# 2364_Adapter.net
KiCad netlist of a schematic drawn in Altium Designer
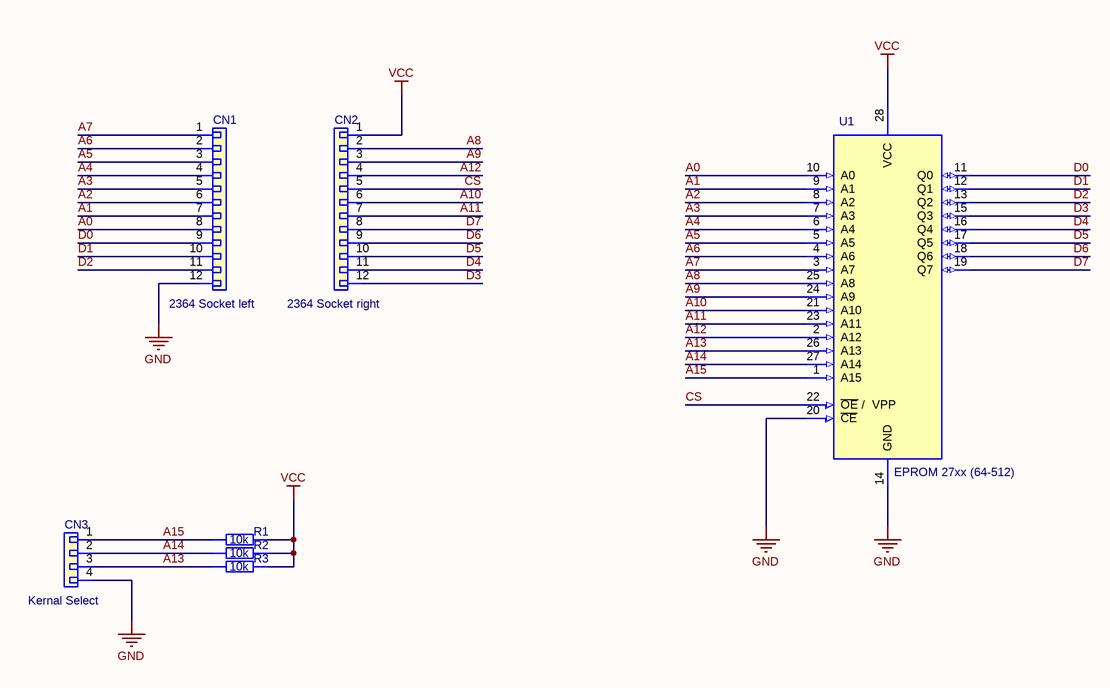
[diagram p0: 2364 Adapter.SchDoc]

(export (version "E")
  (design (tool "Eeschema 10.0.6"))
  (components
    (comp (ref "CN1")
      (value "2364 Socket left")
      (footprint "Pin Header 01x12 2.54mm Horizontal Male")
      (description "CONN HEADER .100 SNGL STR 12POS")
      (libsource (lib "") (part "CONN 01x12_1"))
    )
    (comp (ref "CN2")
      (value "2364 Socket right")
      (footprint "Pin Header 01x12 2.54mm Horizontal Male")
      (description "CONN HEADER .100 SNGL STR 12POS")
      (libsource (lib "PCB-Tech Cloud") (part "CONN 01x12"))
    )
    (comp (ref "CN3")
      (value "Kernal Select")
      (footprint "Pin Header 01x04 2.54mm Horizontal Male")
      (description "CONN HEADER .100\" SNGL STR 4POS")
      (libsource (lib "PCB-Tech Cloud") (part "CONN 01x04"))
    )
    (comp (ref "R1")
      (value "10k")
      (footprint "10 kOhm R Axial DIN0207 L6.3mm D2.5mm P7.62mm Horizontal")
      (description "RES 10K OHM 1/4W 5% AXIAL")
      (fields (field (name "TOLERANCE") "5%"))
      (libsource (lib "PCB-Tech Cloud") (part "Resistor"))
    )
    (comp (ref "R2")
      (value "10k")
      (footprint "10 kOhm R Axial DIN0207 L6.3mm D2.5mm P7.62mm Horizontal")
      (description "RES 10K OHM 1/4W 5% AXIAL")
      (fields (field (name "TOLERANCE") "5%"))
      (libsource (lib "PCB-Tech Cloud") (part "Resistor"))
    )
    (comp (ref "R3")
      (value "10k")
      (footprint "10 kOhm R Axial DIN0207 L6.3mm D2.5mm P7.62mm Horizontal")
      (description "RES 10K OHM 1/4W 5% AXIAL")
      (fields (field (name "TOLERANCE") "5%"))
      (libsource (lib "PCB-Tech Cloud") (part "Resistor"))
    )
    (comp (ref "U1")
      (value "EPROM 27xx (64-512)")
      (footprint "Winbond W27C512-45Z DIP-28 with Socket")
      (description "IC EEPROM 512KBIT 45NS 28DIP")
      (libsource (lib "PCB-Tech Cloud") (part "28PIN 64kx8 EEPROM W27C512"))
    )
  )
  (nets
    (net (code "1") (name "/A0") (class "Default")
      (node (ref "CN1") (pin "8") (pinfunction "8_8") (pintype "passive"))
      (node (ref "U1") (pin "10") (pinfunction "A0_10") (pintype "input"))
    )
    (net (code "2") (name "/A1") (class "Default")
      (node (ref "CN1") (pin "7") (pinfunction "7_7") (pintype "passive"))
      (node (ref "U1") (pin "9") (pinfunction "A1_9") (pintype "input"))
    )
    (net (code "3") (name "/A2") (class "Default")
      (node (ref "CN1") (pin "6") (pinfunction "6_6") (pintype "passive"))
      (node (ref "U1") (pin "8") (pinfunction "A2_8") (pintype "input"))
    )
    (net (code "4") (name "/A3") (class "Default")
      (node (ref "CN1") (pin "5") (pinfunction "5_5") (pintype "passive"))
      (node (ref "U1") (pin "7") (pinfunction "A3_7") (pintype "input"))
    )
    (net (code "5") (name "/A4") (class "Default")
      (node (ref "CN1") (pin "4") (pinfunction "4_4") (pintype "passive"))
      (node (ref "U1") (pin "6") (pinfunction "A4_6") (pintype "input"))
    )
    (net (code "6") (name "/A5") (class "Default")
      (node (ref "CN1") (pin "3") (pinfunction "3_3") (pintype "passive"))
      (node (ref "U1") (pin "5") (pinfunction "A5_5") (pintype "input"))
    )
    (net (code "7") (name "/A6") (class "Default")
      (node (ref "CN1") (pin "2") (pinfunction "2_2") (pintype "passive"))
      (node (ref "U1") (pin "4") (pinfunction "A6_4") (pintype "input"))
    )
    (net (code "8") (name "/A7") (class "Default")
      (node (ref "CN1") (pin "1") (pinfunction "1_1") (pintype "passive"))
      (node (ref "U1") (pin "3") (pinfunction "A7_3") (pintype "input"))
    )
    (net (code "9") (name "/A8") (class "Default")
      (node (ref "CN2") (pin "2") (pinfunction "2_2") (pintype "passive"))
      (node (ref "U1") (pin "25") (pinfunction "A8_25") (pintype "input"))
    )
    (net (code "10") (name "/A9") (class "Default")
      (node (ref "CN2") (pin "3") (pinfunction "3_3") (pintype "passive"))
      (node (ref "U1") (pin "24") (pinfunction "A9_24") (pintype "input"))
    )
    (net (code "11") (name "/A10") (class "Default")
      (node (ref "CN2") (pin "6") (pinfunction "6_6") (pintype "passive"))
      (node (ref "U1") (pin "21") (pinfunction "A10_21") (pintype "input"))
    )
    (net (code "12") (name "/A11") (class "Default")
      (node (ref "CN2") (pin "7") (pinfunction "7_7") (pintype "passive"))
      (node (ref "U1") (pin "23") (pinfunction "A11_23") (pintype "input"))
    )
    (net (code "13") (name "/A12") (class "Default")
      (node (ref "CN2") (pin "4") (pinfunction "4_4") (pintype "passive"))
      (node (ref "U1") (pin "2") (pinfunction "A12_2") (pintype "input"))
    )
    (net (code "14") (name "/A13") (class "Default")
      (node (ref "CN3") (pin "3") (pinfunction "3_3") (pintype "passive"))
      (node (ref "R3") (pin "1") (pinfunction "1_1") (pintype "passive"))
      (node (ref "U1") (pin "26") (pinfunction "A13_26") (pintype "input"))
    )
    (net (code "15") (name "/A14") (class "Default")
      (node (ref "CN3") (pin "2") (pinfunction "2_2") (pintype "passive"))
      (node (ref "R2") (pin "1") (pinfunction "1_1") (pintype "passive"))
      (node (ref "U1") (pin "27") (pinfunction "A14_27") (pintype "input"))
    )
    (net (code "16") (name "/A15") (class "Default")
      (node (ref "CN3") (pin "1") (pinfunction "1_1") (pintype "passive"))
      (node (ref "R1") (pin "1") (pinfunction "1_1") (pintype "passive"))
      (node (ref "U1") (pin "1") (pinfunction "A15_1") (pintype "input"))
    )
    (net (code "17") (name "/CS") (class "Default")
      (node (ref "CN2") (pin "5") (pinfunction "5_5") (pintype "passive"))
      (node (ref "U1") (pin "22") (pinfunction "~{OE}_/__VPP_22") (pintype "input"))
    )
    (net (code "18") (name "/D0") (class "Default")
      (node (ref "CN1") (pin "9") (pinfunction "9_9") (pintype "passive"))
      (node (ref "U1") (pin "11") (pinfunction "Q0_11") (pintype "bidirectional"))
    )
    (net (code "19") (name "/D1") (class "Default")
      (node (ref "CN1") (pin "10") (pinfunction "10_10") (pintype "passive"))
      (node (ref "U1") (pin "12") (pinfunction "Q1_12") (pintype "bidirectional"))
    )
    (net (code "20") (name "/D2") (class "Default")
      (node (ref "CN1") (pin "11") (pinfunction "11_11") (pintype "passive"))
      (node (ref "U1") (pin "13") (pinfunction "Q2_13") (pintype "bidirectional"))
    )
    (net (code "21") (name "/D3") (class "Default")
      (node (ref "CN2") (pin "12") (pinfunction "12_12") (pintype "passive"))
      (node (ref "U1") (pin "15") (pinfunction "Q3_15") (pintype "bidirectional"))
    )
    (net (code "22") (name "/D4") (class "Default")
      (node (ref "CN2") (pin "11") (pinfunction "11_11") (pintype "passive"))
      (node (ref "U1") (pin "16") (pinfunction "Q4_16") (pintype "bidirectional"))
    )
    (net (code "23") (name "/D5") (class "Default")
      (node (ref "CN2") (pin "10") (pinfunction "10_10") (pintype "passive"))
      (node (ref "U1") (pin "17") (pinfunction "Q5_17") (pintype "bidirectional"))
    )
    (net (code "24") (name "/D6") (class "Default")
      (node (ref "CN2") (pin "9") (pinfunction "9_9") (pintype "passive"))
      (node (ref "U1") (pin "18") (pinfunction "Q6_18") (pintype "bidirectional"))
    )
    (net (code "25") (name "/D7") (class "Default")
      (node (ref "CN2") (pin "8") (pinfunction "8_8") (pintype "passive"))
      (node (ref "U1") (pin "19") (pinfunction "Q7_19") (pintype "bidirectional"))
    )
    (net (code "26") (name "GND") (class "Default")
      (node (ref "CN1") (pin "12") (pinfunction "12_12") (pintype "passive"))
      (node (ref "CN3") (pin "4") (pinfunction "4_4") (pintype "passive"))
      (node (ref "U1") (pin "14") (pinfunction "GND_14") (pintype "passive"))
      (node (ref "U1") (pin "20") (pinfunction "~{CE}_20") (pintype "input"))
    )
    (net (code "27") (name "VCC") (class "Default")
      (node (ref "CN2") (pin "1") (pinfunction "1_1") (pintype "passive"))
      (node (ref "R1") (pin "2") (pinfunction "2_2") (pintype "passive"))
      (node (ref "R2") (pin "2") (pinfunction "2_2") (pintype "passive"))
      (node (ref "R3") (pin "2") (pinfunction "2_2") (pintype "passive"))
      (node (ref "U1") (pin "28") (pinfunction "VCC_28") (pintype "power_in"))
    )
  )
)
